# OneStep.net
KiCad netlist of a schematic drawn in Altium Designer
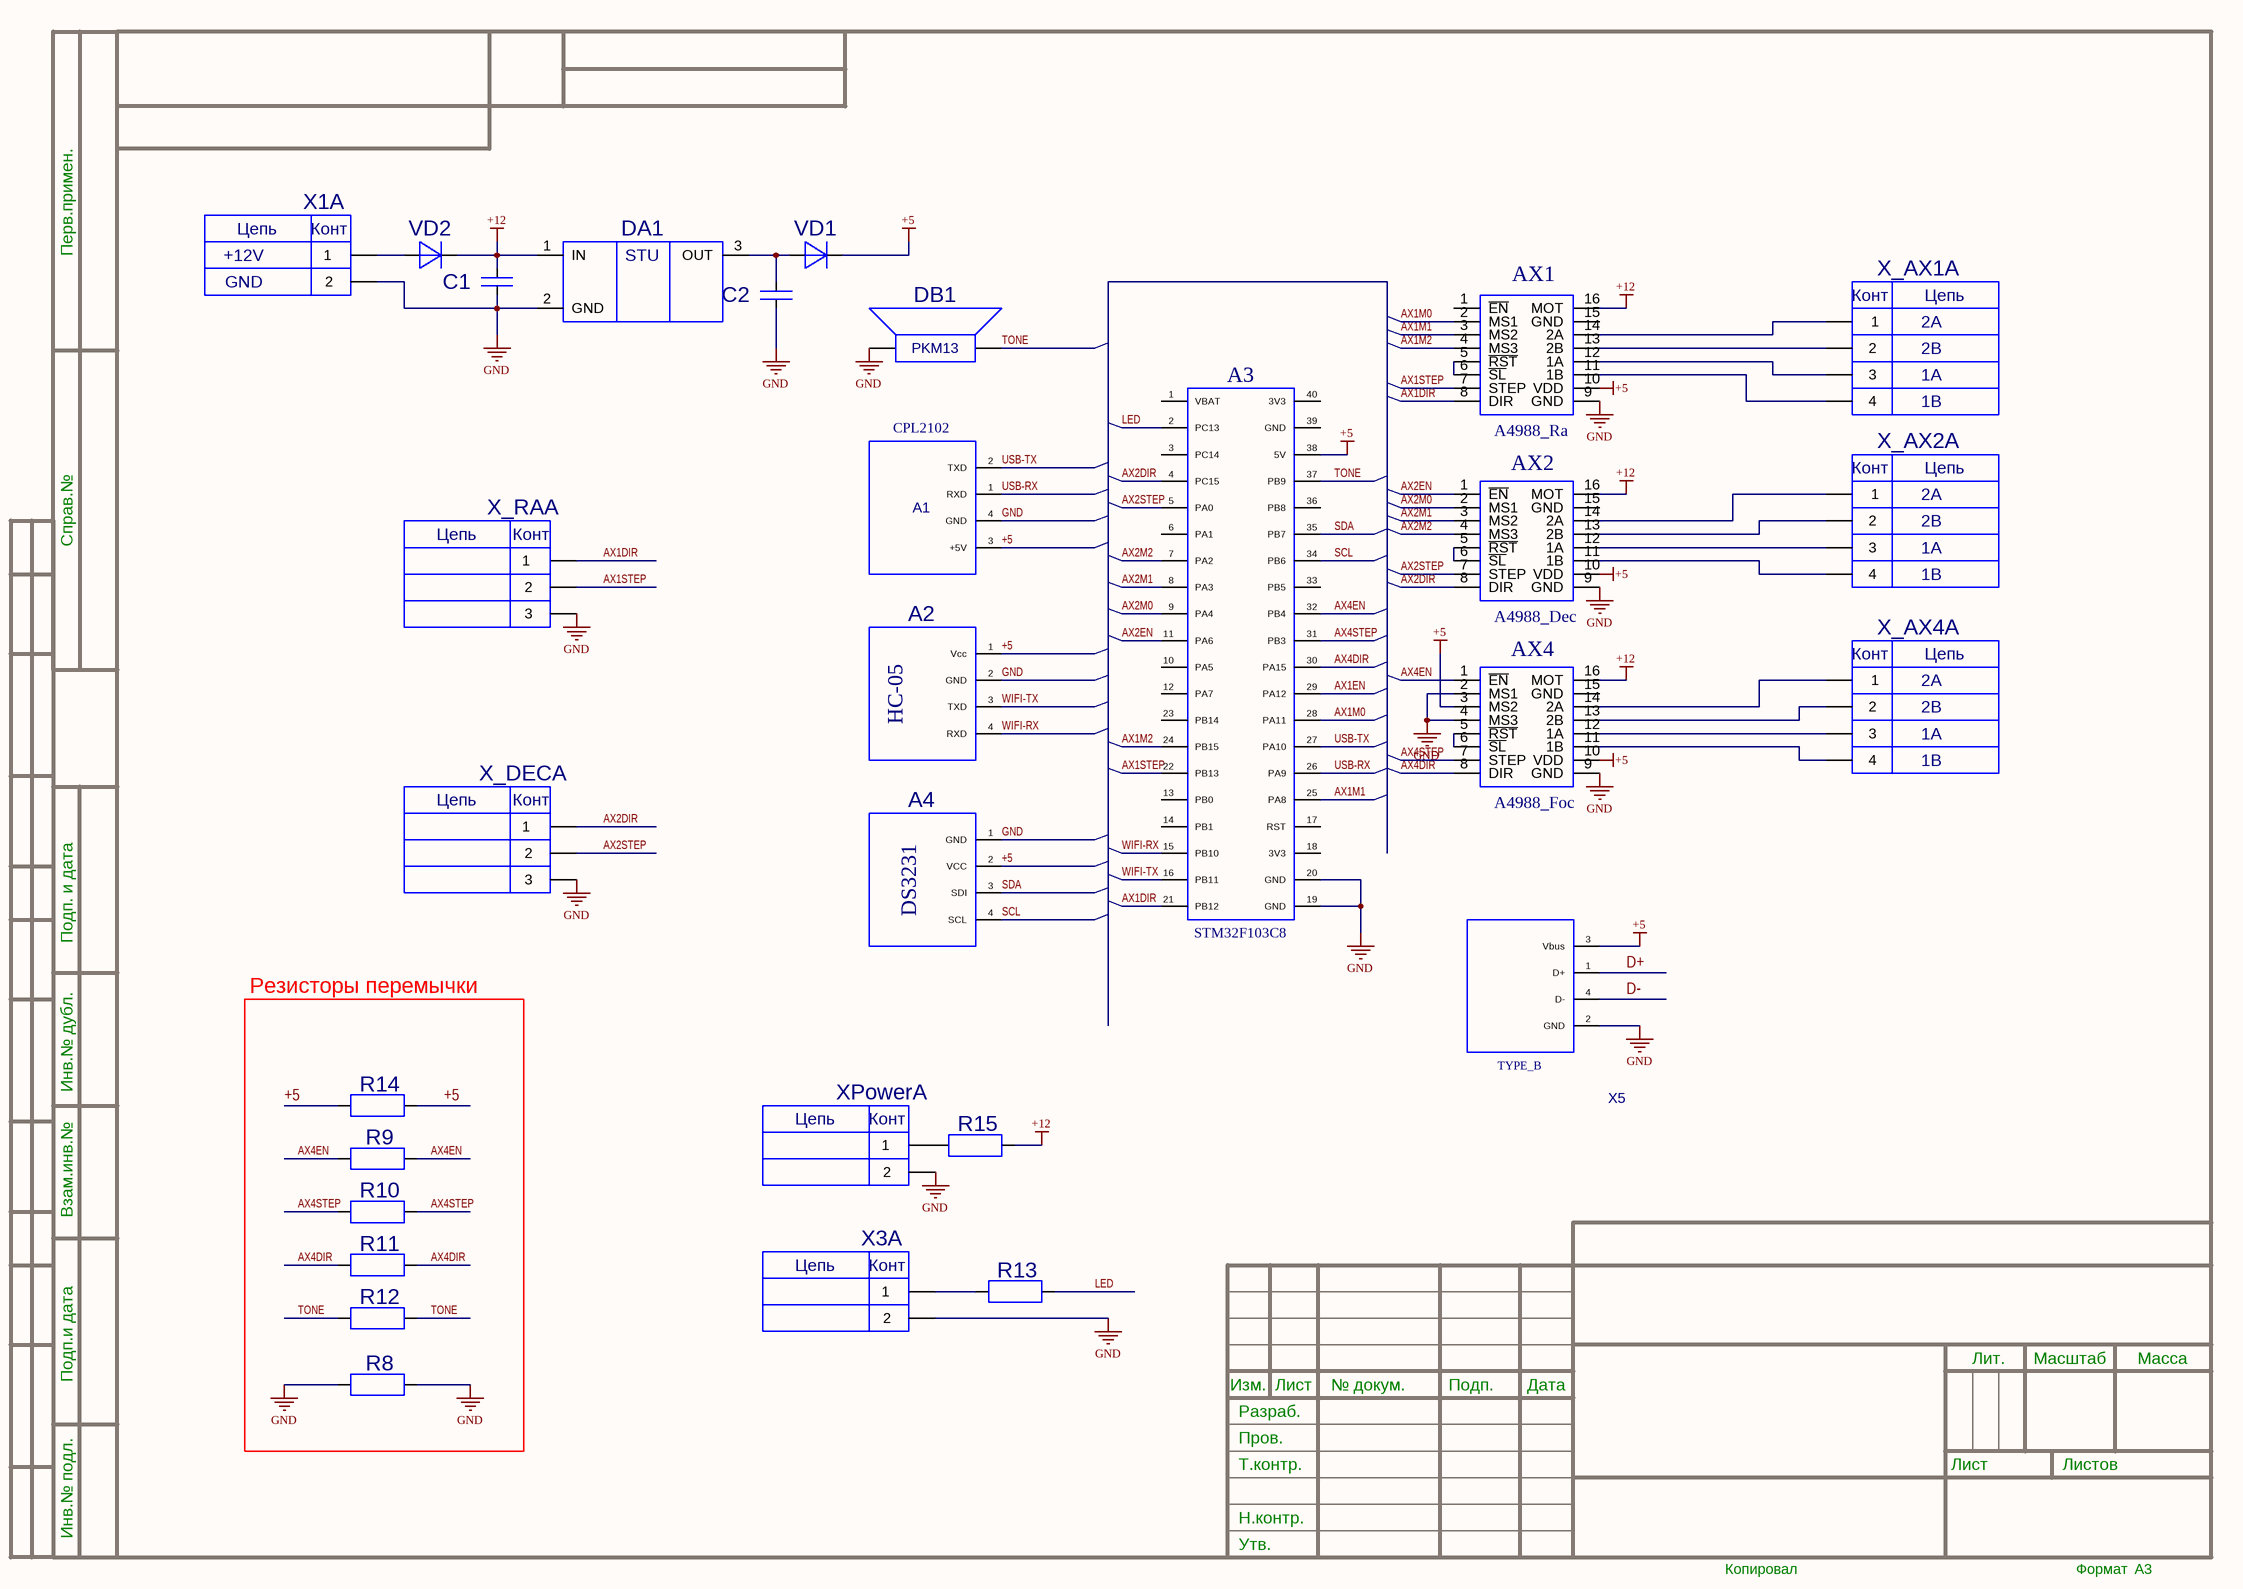
[diagram p0: OneStep.SchDoc]

(export (version "E")
  (design (tool "Eeschema 10.0.6"))
  (components
    (comp (ref "A1")
      (value "CPL2102")
      (footprint "CP2102")
      (fields
        (field (name "MANUFACTURER") "Texas Instruments")
        (field (name "COMPONENTLINK1URL") "c:\\Dataseets\\Микросхемы\\По фирмам\\Avago Technologies\\HCPL-4100.pdf")
      )
      (libsource (lib "nanoArduino") (part "CPL2102"))
    )
    (comp (ref "A2")
      (value "HC-05")
      (footprint "HC-05")
      (fields
        (field (name "MANUFACTURER") "Texas Instruments")
        (field (name "COMPONENTLINK1URL") "c:\\Dataseets\\Микросхемы\\По фирмам\\Avago Technologies\\HCPL-4100.pdf")
      )
      (libsource (lib "nanoArduino") (part "HC-05"))
    )
    (comp (ref "A3")
      (value "STM32F103C8")
      (footprint "STM32BLUE_PILL")
      (fields
        (field (name "MANUFACTURER") "NXP")
        (field (name "COMPONENTLINK1URL") "c:\\Dataseets\\Микросхемы\\По фирмам\\Avago Technologies\\HCPL-4100.pdf")
      )
      (libsource (lib "Horizont_11_12_2017") (part "STM32BLUE_PILL"))
    )
    (comp (ref "A4")
      (value "DS3231")
      (footprint "DS3231")
      (fields
        (field (name "MANUFACTURER") "Texas Instruments")
        (field (name "COMPONENTLINK1URL") "c:\\Dataseets\\Микросхемы\\По фирмам\\Avago Technologies\\HCPL-4100.pdf")
      )
      (libsource (lib "nanoArduino") (part "DS3231"))
    )
    (comp (ref "AX1")
      (value "A4988_Ra")
      (footprint "A4899")
      (description "STEP Motor Driver")
      (fields
        (field (name "PART NUMBER") "DRV8825")
        (field (name "HELPURL") "D:\\Local_view\\PDM\\Справочники\\Перечень ЭРИ\\Документация\\max1316-max1326.pdf")
      )
      (libsource (lib "nanoArduino") (part "DRV8825"))
    )
    (comp (ref "AX2")
      (value "A4988_Dec")
      (footprint "A4899")
      (description "STEP Motor Driver")
      (fields
        (field (name "PART NUMBER") "DRV8825")
        (field (name "HELPURL") "D:\\Local_view\\PDM\\Справочники\\Перечень ЭРИ\\Документация\\max1316-max1326.pdf")
      )
      (libsource (lib "nanoArduino") (part "DRV8825"))
    )
    (comp (ref "AX4")
      (value "A4988_Foc")
      (footprint "A4899")
      (description "STEP Motor Driver")
      (fields
        (field (name "PART NUMBER") "DRV8825")
        (field (name "HELPURL") "D:\\Local_view\\PDM\\Справочники\\Перечень ЭРИ\\Документация\\max1316-max1326.pdf")
      )
      (libsource (lib "nanoArduino") (part "DRV8825"))
    )
    (comp (ref "C1")
      (value "4,7мкФ")
      (footprint "C1206H19")
      (description "Керамический ЧИП конденсатор")
      (fields
        (field (name "PART NUMBER") "1206 X7R 50В 4,7мкФ")
        (field (name "TOLERANCE") "±10%")
        (field (name "HELPURL") "D:\\local_view\\PDM\\Справочники\\Перечень ЭРИ\\Документация\\Конденсаторы\\Керамические\\ЧИП\\0201-1812_TY.pdf")
      )
      (libsource (lib "Library") (part "C_nonpolar"))
    )
    (comp (ref "C2")
      (value "4,7мкФ")
      (footprint "C1206H19")
      (description "Керамический ЧИП конденсатор")
      (fields
        (field (name "PART NUMBER") "1206 X7R 50В 4,7мкФ")
        (field (name "TOLERANCE") "±10%")
        (field (name "HELPURL") "D:\\local_view\\PDM\\Справочники\\Перечень ЭРИ\\Документация\\Конденсаторы\\Керамические\\ЧИП\\0201-1812_TY.pdf")
      )
      (libsource (lib "Library") (part "C_nonpolar"))
    )
    (comp (ref "DA1")
      (value "L7805CD2T")
      (footprint "D2PAK")
      (description "Positive voltage regulator")
      (fields
        (field (name "MANUFACTURER") "ST Microelectronics")
        (field (name "HELPURL") "D:\\local_view\\PDM\\Справочники\\Перечень ЭРИ\\Документация\\Микросхемы\\Линейные стабилизаторы напряжения\\L7800_STMicroelectronics.pdf")
      )
      (libsource (lib "Library") (part "STU"))
    )
    (comp (ref "DB1")
      (value "PKM13")
      (footprint "PKM13")
      (description "=Description")
      (libsource (lib "nanoArduino") (part "PKM13"))
    )
    (comp (ref "R8")
      (value "0 Ом")
      (footprint "R1206H07")
      (description "Постоянный ЧИП резистор")
      (fields
        (field (name "PART NUMBER") "1206 0 Ом±5%")
        (field (name "POWER") "0.25W")
        (field (name "HELPURL") "D:\\Local_view\\PDM\\Справочники\\Перечень ЭРИ\\Документация\\Резисторы\\Постоянные\\ЧИП\\RC1206_yageo.pdf")
      )
      (libsource (lib "Library") (part "R"))
    )
    (comp (ref "R9")
      (value "0 Ом")
      (footprint "R1206H07")
      (description "Постоянный ЧИП резистор")
      (fields
        (field (name "PART NUMBER") "1206 0 Ом±5%")
        (field (name "POWER") "0.25W")
        (field (name "HELPURL") "D:\\Local_view\\PDM\\Справочники\\Перечень ЭРИ\\Документация\\Резисторы\\Постоянные\\ЧИП\\RC1206_yageo.pdf")
      )
      (libsource (lib "Library") (part "R"))
    )
    (comp (ref "R10")
      (value "0 Ом")
      (footprint "R1206H07")
      (description "Постоянный ЧИП резистор")
      (fields
        (field (name "PART NUMBER") "1206 0 Ом±5%")
        (field (name "POWER") "0.25W")
        (field (name "HELPURL") "D:\\Local_view\\PDM\\Справочники\\Перечень ЭРИ\\Документация\\Резисторы\\Постоянные\\ЧИП\\RC1206_yageo.pdf")
      )
      (libsource (lib "Library") (part "R"))
    )
    (comp (ref "R11")
      (value "0 Ом")
      (footprint "R1206H07")
      (description "Постоянный ЧИП резистор")
      (fields
        (field (name "PART NUMBER") "1206 0 Ом±5%")
        (field (name "POWER") "0.25W")
        (field (name "HELPURL") "D:\\Local_view\\PDM\\Справочники\\Перечень ЭРИ\\Документация\\Резисторы\\Постоянные\\ЧИП\\RC1206_yageo.pdf")
      )
      (libsource (lib "Library") (part "R"))
    )
    (comp (ref "R12")
      (value "0 Ом")
      (footprint "R1206H07")
      (description "Постоянный ЧИП резистор")
      (fields
        (field (name "PART NUMBER") "1206 0 Ом±5%")
        (field (name "POWER") "0.25W")
        (field (name "HELPURL") "D:\\Local_view\\PDM\\Справочники\\Перечень ЭРИ\\Документация\\Резисторы\\Постоянные\\ЧИП\\RC1206_yageo.pdf")
      )
      (libsource (lib "Library") (part "R"))
    )
    (comp (ref "R13")
      (value "0 Ом")
      (footprint "R1206H07")
      (description "Постоянный ЧИП резистор")
      (fields
        (field (name "PART NUMBER") "1206 0 Ом±5%")
        (field (name "POWER") "0.25W")
        (field (name "HELPURL") "D:\\Local_view\\PDM\\Справочники\\Перечень ЭРИ\\Документация\\Резисторы\\Постоянные\\ЧИП\\RC1206_yageo.pdf")
      )
      (libsource (lib "Library") (part "R"))
    )
    (comp (ref "R14")
      (value "0 Ом")
      (footprint "R1206H07")
      (description "Постоянный ЧИП резистор")
      (fields
        (field (name "PART NUMBER") "1206 0 Ом±5%")
        (field (name "POWER") "0.25W")
        (field (name "HELPURL") "D:\\Local_view\\PDM\\Справочники\\Перечень ЭРИ\\Документация\\Резисторы\\Постоянные\\ЧИП\\RC1206_yageo.pdf")
      )
      (libsource (lib "Library") (part "R"))
    )
    (comp (ref "R15")
      (value "24кОм")
      (footprint "R1206H07")
      (description "Постоянный ЧИП резистор")
      (fields
        (field (name "PART NUMBER") "1206 24кОм±5%")
        (field (name "POWER") "0.25W")
        (field (name "HELPURL") "D:\\Local_view\\PDM\\Справочники\\Перечень ЭРИ\\Документация\\Резисторы\\Постоянные\\ЧИП\\RC1206_yageo.pdf")
      )
      (libsource (lib "Library") (part "R"))
    )
    (comp (ref "VD1")
      (value "US1J")
      (footprint "SMA")
      (description "Surface Mount Ultra Fast Rectifier")
      (fields
        (field (name "MANUFACTURER") "Vishay")
        (field (name "HELPURL") "D:\\local_view\\PDM\\Справочники\\Перечень ЭРИ\\Документация\\Диоды\\Выпрямительные и импульсные диоды\\US1A-US1M_Vishay.pdf")
      )
      (libsource (lib "Library") (part "VD"))
    )
    (comp (ref "VD2")
      (value "US1J")
      (footprint "SMA")
      (description "Surface Mount Ultra Fast Rectifier")
      (fields
        (field (name "MANUFACTURER") "Vishay")
        (field (name "HELPURL") "D:\\local_view\\PDM\\Справочники\\Перечень ЭРИ\\Документация\\Диоды\\Выпрямительные и импульсные диоды\\US1A-US1M_Vishay.pdf")
      )
      (libsource (lib "Library") (part "VD"))
    )
    (comp (ref "X1")
      (value "PLS-02")
      (footprint "PLS-02")
      (description "Вилка на плату прямая шаг 2,54 мм 1 ряд")
      (fields
        (field (name "HELPURL") "D:\\Local_view\\PDM\\Справочники\\Перечень ЭРИ\\Документация\\Соединители\\Прямоугольные\\pld_pls.pdf")
      )
      (libsource (lib "Library") (part "CONT2"))
    )
    (comp (ref "X3")
      (value "PLS-02")
      (footprint "PLS-02")
      (description "Вилка на плату прямая шаг 2,54 мм 1 ряд")
      (fields
        (field (name "HELPURL") "D:\\Local_view\\PDM\\Справочники\\Перечень ЭРИ\\Документация\\Соединители\\Прямоугольные\\pld_pls.pdf")
      )
      (libsource (lib "Library") (part "CONT2"))
    )
    (comp (ref "X5")
      (value "TYPE_B")
      (footprint "Type_B")
      (description "USB_type_B")
      (fields
        (field (name "MANUFACTURER") "Texas Instruments")
        (field (name "VALUESCH") "TYPE_B")
        (field (name "COMPONENTLINK1URL") "c:\\Dataseets\\Микросхемы\\По фирмам\\Avago Technologies\\HCPL-4100.pdf")
      )
      (libsource (lib "nanoArduino") (part "USB_type_B"))
    )
    (comp (ref "XPower")
      (value "PLS-02")
      (footprint "PLS-02")
      (description "Вилка на плату прямая шаг 2,54 мм 1 ряд")
      (fields
        (field (name "HELPURL") "D:\\Local_view\\PDM\\Справочники\\Перечень ЭРИ\\Документация\\Соединители\\Прямоугольные\\pld_pls.pdf")
      )
      (libsource (lib "Library") (part "CONT2"))
    )
    (comp (ref "X_AX1")
      (value "PLS-04")
      (footprint "PLS-04")
      (description "Вилка на плату прямая шаг 2,54 мм 1 ряд")
      (fields
        (field (name "HELPURL") "D:\\Local_view\\PDM\\Справочники\\Перечень ЭРИ\\Документация\\Соединители\\Прямоугольные\\pld_pls.pdf")
      )
      (libsource (lib "Library") (part "CONT4"))
    )
    (comp (ref "X_AX2")
      (value "PLS-04")
      (footprint "PLS-04")
      (description "Вилка на плату прямая шаг 2,54 мм 1 ряд")
      (fields
        (field (name "HELPURL") "D:\\Local_view\\PDM\\Справочники\\Перечень ЭРИ\\Документация\\Соединители\\Прямоугольные\\pld_pls.pdf")
      )
      (libsource (lib "Library") (part "CONT4"))
    )
    (comp (ref "X_AX4")
      (value "PLS-04")
      (footprint "PLS-04")
      (description "Вилка на плату прямая шаг 2,54 мм 1 ряд")
      (fields
        (field (name "HELPURL") "D:\\Local_view\\PDM\\Справочники\\Перечень ЭРИ\\Документация\\Соединители\\Прямоугольные\\pld_pls.pdf")
      )
      (libsource (lib "Library") (part "CONT4"))
    )
    (comp (ref "X_DEC")
      (value "DG128-5.0-03P")
      (footprint "DG128-5.0-03")
      (description "Винтовой клеммник, \r\n3 контакта")
      (fields
        (field (name "PART NUMBER") "DG128-5.0-03P-14")
        (field (name "MANUFACTURER") "DEGSON")
        (field (name "HELPURL") "D:\\Local_view\\PDM\\Справочники\\Перечень ЭРИ\\Документация\\Соединители\\Клеммники\\DG128-5.0.pdf")
      )
      (libsource (lib "Library") (part "CONT3"))
    )
    (comp (ref "X_RA")
      (value "DG128-5.0-03P")
      (footprint "DG128-5.0-03")
      (description "Винтовой клеммник, \r\n3 контакта")
      (fields
        (field (name "PART NUMBER") "DG128-5.0-03P-14")
        (field (name "MANUFACTURER") "DEGSON")
        (field (name "HELPURL") "D:\\Local_view\\PDM\\Справочники\\Перечень ЭРИ\\Документация\\Соединители\\Клеммники\\DG128-5.0.pdf")
      )
      (libsource (lib "Library") (part "CONT3"))
    )
  )
  (nets
    (net (code "1") (name "+5") (class "Default")
      (node (ref "A1") (pin "3") (pinfunction "+5V_3") (pintype "passive"))
      (node (ref "A2") (pin "1") (pinfunction "Vcc_1") (pintype "passive"))
      (node (ref "A3") (pin "38") (pinfunction "5V_38") (pintype "passive"))
      (node (ref "A4") (pin "2") (pinfunction "VCC_2") (pintype "passive"))
      (node (ref "AX1") (pin "10") (pinfunction "VDD_10") (pintype "passive"))
      (node (ref "AX2") (pin "10") (pinfunction "VDD_10") (pintype "passive"))
      (node (ref "AX4") (pin "10") (pinfunction "VDD_10") (pintype "passive"))
      (node (ref "AX4") (pin "3") (pinfunction "MS2_3") (pintype "passive"))
      (node (ref "R14") (pin "1") (pinfunction "1_1") (pintype "passive"))
      (node (ref "R14") (pin "2") (pinfunction "2_2") (pintype "passive"))
      (node (ref "VD1") (pin "2") (pinfunction "-_2") (pintype "passive"))
      (node (ref "X5") (pin "3") (pinfunction "Vbus_3") (pintype "passive"))
    )
    (net (code "2") (name "+12") (class "Default")
      (node (ref "AX1") (pin "16") (pinfunction "MOT_16") (pintype "passive"))
      (node (ref "AX2") (pin "16") (pinfunction "MOT_16") (pintype "passive"))
      (node (ref "AX4") (pin "16") (pinfunction "MOT_16") (pintype "passive"))
      (node (ref "C1") (pin "2") (pinfunction "2_2") (pintype "passive"))
      (node (ref "DA1") (pin "1") (pinfunction "IN_1") (pintype "passive"))
      (node (ref "R15") (pin "2") (pinfunction "2_2") (pintype "passive"))
      (node (ref "VD2") (pin "2") (pinfunction "-_2") (pintype "passive"))
    )
    (net (code "3") (name "/AX1DIR") (class "Default")
      (node (ref "A3") (pin "21") (pinfunction "PB12_21") (pintype "passive"))
      (node (ref "AX1") (pin "8") (pinfunction "DIR_8") (pintype "passive"))
      (node (ref "X_RA") (pin "1") (pinfunction "1_1") (pintype "passive"))
    )
    (net (code "4") (name "/AX1EN") (class "Default")
      (node (ref "A3") (pin "29") (pinfunction "PA12_29") (pintype "passive"))
    )
    (net (code "5") (name "/AX1M0") (class "Default")
      (node (ref "A3") (pin "28") (pinfunction "PA11_28") (pintype "passive"))
      (node (ref "AX1") (pin "2") (pinfunction "MS1_2") (pintype "passive"))
    )
    (net (code "6") (name "/AX1M1") (class "Default")
      (node (ref "A3") (pin "25") (pinfunction "PA8_25") (pintype "passive"))
      (node (ref "AX1") (pin "3") (pinfunction "MS2_3") (pintype "passive"))
    )
    (net (code "7") (name "/AX1M2") (class "Default")
      (node (ref "A3") (pin "24") (pinfunction "PB15_24") (pintype "passive"))
      (node (ref "AX1") (pin "4") (pinfunction "MS3_4") (pintype "passive"))
    )
    (net (code "8") (name "/AX1STEP") (class "Default")
      (node (ref "A3") (pin "22") (pinfunction "PB13_22") (pintype "passive"))
      (node (ref "AX1") (pin "7") (pinfunction "STEP_7") (pintype "passive"))
      (node (ref "X_RA") (pin "2") (pinfunction "2_2") (pintype "passive"))
    )
    (net (code "9") (name "/AX2DIR") (class "Default")
      (node (ref "A3") (pin "4") (pinfunction "PC15_4") (pintype "passive"))
      (node (ref "AX2") (pin "8") (pinfunction "DIR_8") (pintype "passive"))
      (node (ref "X_DEC") (pin "1") (pinfunction "1_1") (pintype "passive"))
    )
    (net (code "10") (name "/AX2EN") (class "Default")
      (node (ref "A3") (pin "11") (pinfunction "PA6_11") (pintype "passive"))
      (node (ref "AX2") (pin "1") (pinfunction "EN_1") (pintype "passive"))
    )
    (net (code "11") (name "/AX2M0") (class "Default")
      (node (ref "A3") (pin "9") (pinfunction "PA4_9") (pintype "passive"))
      (node (ref "AX2") (pin "2") (pinfunction "MS1_2") (pintype "passive"))
    )
    (net (code "12") (name "/AX2M1") (class "Default")
      (node (ref "A3") (pin "8") (pinfunction "PA3_8") (pintype "passive"))
      (node (ref "AX2") (pin "3") (pinfunction "MS2_3") (pintype "passive"))
    )
    (net (code "13") (name "/AX2M2") (class "Default")
      (node (ref "A3") (pin "7") (pinfunction "PA2_7") (pintype "passive"))
      (node (ref "AX2") (pin "4") (pinfunction "MS3_4") (pintype "passive"))
    )
    (net (code "14") (name "/AX2STEP") (class "Default")
      (node (ref "A3") (pin "5") (pinfunction "PA0_5") (pintype "passive"))
      (node (ref "AX2") (pin "7") (pinfunction "STEP_7") (pintype "passive"))
      (node (ref "X_DEC") (pin "2") (pinfunction "2_2") (pintype "passive"))
    )
    (net (code "15") (name "/AX4DIR") (class "Default")
      (node (ref "A3") (pin "30") (pinfunction "PA15_30") (pintype "passive"))
      (node (ref "AX4") (pin "8") (pinfunction "DIR_8") (pintype "passive"))
      (node (ref "R11") (pin "1") (pinfunction "1_1") (pintype "passive"))
      (node (ref "R11") (pin "2") (pinfunction "2_2") (pintype "passive"))
    )
    (net (code "16") (name "/AX4EN") (class "Default")
      (node (ref "A3") (pin "32") (pinfunction "PB4_32") (pintype "passive"))
      (node (ref "AX4") (pin "1") (pinfunction "EN_1") (pintype "passive"))
      (node (ref "R9") (pin "1") (pinfunction "1_1") (pintype "passive"))
      (node (ref "R9") (pin "2") (pinfunction "2_2") (pintype "passive"))
    )
    (net (code "17") (name "/AX4STEP") (class "Default")
      (node (ref "A3") (pin "31") (pinfunction "PB3_31") (pintype "passive"))
      (node (ref "AX4") (pin "7") (pinfunction "STEP_7") (pintype "passive"))
      (node (ref "R10") (pin "1") (pinfunction "1_1") (pintype "passive"))
      (node (ref "R10") (pin "2") (pinfunction "2_2") (pintype "passive"))
    )
    (net (code "18") (name "/D+") (class "Default")
      (node (ref "X5") (pin "1") (pinfunction "D+_1") (pintype "passive"))
    )
    (net (code "19") (name "/D-") (class "Default")
      (node (ref "X5") (pin "4") (pinfunction "D-_4") (pintype "passive"))
    )
    (net (code "20") (name "/LED") (class "Default")
      (node (ref "A3") (pin "2") (pinfunction "PC13_2") (pintype "passive"))
      (node (ref "R13") (pin "2") (pinfunction "2_2") (pintype "passive"))
    )
    (net (code "21") (name "/SCL") (class "Default")
      (node (ref "A3") (pin "34") (pinfunction "PB6_34") (pintype "passive"))
      (node (ref "A4") (pin "4") (pinfunction "SCL_4") (pintype "passive"))
    )
    (net (code "22") (name "/SDA") (class "Default")
      (node (ref "A3") (pin "35") (pinfunction "PB7_35") (pintype "passive"))
      (node (ref "A4") (pin "3") (pinfunction "SDI_3") (pintype "passive"))
    )
    (net (code "23") (name "/TONE") (class "Default")
      (node (ref "A3") (pin "37") (pinfunction "PB9_37") (pintype "passive"))
      (node (ref "DB1") (pin "2") (pinfunction "2_2") (pintype "passive"))
      (node (ref "R12") (pin "1") (pinfunction "1_1") (pintype "passive"))
      (node (ref "R12") (pin "2") (pinfunction "2_2") (pintype "passive"))
    )
    (net (code "24") (name "/USB-RX") (class "Default")
      (node (ref "A1") (pin "1") (pinfunction "RXD_1") (pintype "passive"))
      (node (ref "A3") (pin "26") (pinfunction "PA9_26") (pintype "passive"))
    )
    (net (code "25") (name "/USB-TX") (class "Default")
      (node (ref "A1") (pin "2") (pinfunction "TXD_2") (pintype "passive"))
      (node (ref "A3") (pin "27") (pinfunction "PA10_27") (pintype "passive"))
    )
    (net (code "26") (name "/WIFI-RX") (class "Default")
      (node (ref "A2") (pin "4") (pinfunction "RXD_4") (pintype "passive"))
      (node (ref "A3") (pin "15") (pinfunction "PB10_15") (pintype "passive"))
    )
    (net (code "27") (name "/WIFI-TX") (class "Default")
      (node (ref "A2") (pin "3") (pinfunction "TXD_3") (pintype "passive"))
      (node (ref "A3") (pin "16") (pinfunction "PB11_16") (pintype "passive"))
    )
    (net (code "28") (name "GND") (class "Default")
      (node (ref "A1") (pin "4") (pinfunction "GND_4") (pintype "passive"))
      (node (ref "A2") (pin "2") (pinfunction "GND_2") (pintype "passive"))
      (node (ref "A3") (pin "19") (pinfunction "GND_19") (pintype "passive"))
      (node (ref "A3") (pin "20") (pinfunction "GND_20") (pintype "passive"))
      (node (ref "A4") (pin "1") (pinfunction "GND_1") (pintype "passive"))
      (node (ref "AX1") (pin "9") (pinfunction "GND_9") (pintype "passive"))
      (node (ref "AX2") (pin "9") (pinfunction "GND_9") (pintype "passive"))
      (node (ref "AX4") (pin "2") (pinfunction "MS1_2") (pintype "passive"))
      (node (ref "AX4") (pin "4") (pinfunction "MS3_4") (pintype "passive"))
      (node (ref "AX4") (pin "9") (pinfunction "GND_9") (pintype "passive"))
      (node (ref "C1") (pin "1") (pinfunction "1_1") (pintype "passive"))
      (node (ref "C2") (pin "1") (pinfunction "1_1") (pintype "passive"))
      (node (ref "DA1") (pin "2") (pinfunction "GND_2") (pintype "passive"))
      (node (ref "DB1") (pin "1") (pinfunction "1_1") (pintype "passive"))
      (node (ref "R8") (pin "1") (pinfunction "1_1") (pintype "passive"))
      (node (ref "R8") (pin "2") (pinfunction "2_2") (pintype "passive"))
      (node (ref "X1") (pin "2") (pinfunction "2_2") (pintype "passive"))
      (node (ref "X3") (pin "2") (pinfunction "2_2") (pintype "passive"))
      (node (ref "X5") (pin "2") (pinfunction "GND_2") (pintype "passive"))
      (node (ref "XPower") (pin "2") (pinfunction "2_2") (pintype "passive"))
      (node (ref "X_DEC") (pin "3") (pinfunction "3_3") (pintype "passive"))
      (node (ref "X_RA") (pin "3") (pinfunction "3_3") (pintype "passive"))
    )
    (net (code "29") (name "Net-(AX1-1A)") (class "Default")
      (node (ref "AX1") (pin "12") (pinfunction "1A_12") (pintype "passive"))
      (node (ref "X_AX1") (pin "3") (pinfunction "3_3") (pintype "passive"))
    )
    (net (code "30") (name "Net-(AX1-1B)") (class "Default")
      (node (ref "AX1") (pin "11") (pinfunction "1B_11") (pintype "passive"))
      (node (ref "X_AX1") (pin "4") (pinfunction "4_4") (pintype "passive"))
    )
    (net (code "31") (name "Net-(AX1-2A)") (class "Default")
      (node (ref "AX1") (pin "14") (pinfunction "2A_14") (pintype "passive"))
      (node (ref "X_AX1") (pin "1") (pinfunction "1_1") (pintype "passive"))
    )
    (net (code "32") (name "Net-(AX1-2B)") (class "Default")
      (node (ref "AX1") (pin "13") (pinfunction "2B_13") (pintype "passive"))
      (node (ref "X_AX1") (pin "2") (pinfunction "2_2") (pintype "passive"))
    )
    (net (code "33") (name "Net-(AX1-RST)") (class "Default")
      (node (ref "AX1") (pin "5") (pinfunction "RST_5") (pintype "passive"))
      (node (ref "AX1") (pin "6") (pinfunction "SL_6") (pintype "passive"))
    )
    (net (code "34") (name "Net-(AX2-1A)") (class "Default")
      (node (ref "AX2") (pin "12") (pinfunction "1A_12") (pintype "passive"))
      (node (ref "X_AX2") (pin "3") (pinfunction "3_3") (pintype "passive"))
    )
    (net (code "35") (name "Net-(AX2-1B)") (class "Default")
      (node (ref "AX2") (pin "11") (pinfunction "1B_11") (pintype "passive"))
      (node (ref "X_AX2") (pin "4") (pinfunction "4_4") (pintype "passive"))
    )
    (net (code "36") (name "Net-(AX2-2A)") (class "Default")
      (node (ref "AX2") (pin "14") (pinfunction "2A_14") (pintype "passive"))
      (node (ref "X_AX2") (pin "1") (pinfunction "1_1") (pintype "passive"))
    )
    (net (code "37") (name "Net-(AX2-2B)") (class "Default")
      (node (ref "AX2") (pin "13") (pinfunction "2B_13") (pintype "passive"))
      (node (ref "X_AX2") (pin "2") (pinfunction "2_2") (pintype "passive"))
    )
    (net (code "38") (name "Net-(AX2-RST)") (class "Default")
      (node (ref "AX2") (pin "5") (pinfunction "RST_5") (pintype "passive"))
      (node (ref "AX2") (pin "6") (pinfunction "SL_6") (pintype "passive"))
    )
    (net (code "39") (name "Net-(AX4-1A)") (class "Default")
      (node (ref "AX4") (pin "12") (pinfunction "1A_12") (pintype "passive"))
      (node (ref "X_AX4") (pin "3") (pinfunction "3_3") (pintype "passive"))
    )
    (net (code "40") (name "Net-(AX4-1B)") (class "Default")
      (node (ref "AX4") (pin "11") (pinfunction "1B_11") (pintype "passive"))
      (node (ref "X_AX4") (pin "4") (pinfunction "4_4") (pintype "passive"))
    )
    (net (code "41") (name "Net-(AX4-2A)") (class "Default")
      (node (ref "AX4") (pin "14") (pinfunction "2A_14") (pintype "passive"))
      (node (ref "X_AX4") (pin "1") (pinfunction "1_1") (pintype "passive"))
    )
    (net (code "42") (name "Net-(AX4-2B)") (class "Default")
      (node (ref "AX4") (pin "13") (pinfunction "2B_13") (pintype "passive"))
      (node (ref "X_AX4") (pin "2") (pinfunction "2_2") (pintype "passive"))
    )
    (net (code "43") (name "Net-(AX4-RST)") (class "Default")
      (node (ref "AX4") (pin "5") (pinfunction "RST_5") (pintype "passive"))
      (node (ref "AX4") (pin "6") (pinfunction "SL_6") (pintype "passive"))
    )
    (net (code "44") (name "Net-(DA1-OUT)") (class "Default")
      (node (ref "C2") (pin "2") (pinfunction "2_2") (pintype "passive"))
      (node (ref "DA1") (pin "3") (pinfunction "OUT_3") (pintype "passive"))
      (node (ref "VD1") (pin "1") (pinfunction "+_1") (pintype "passive"))
    )
    (net (code "45") (name "Net-(R13-Pad1)") (class "Default")
      (node (ref "R13") (pin "1") (pinfunction "1_1") (pintype "passive"))
      (node (ref "X3") (pin "1") (pinfunction "1_1") (pintype "passive"))
    )
    (net (code "46") (name "Net-(R15-Pad1)") (class "Default")
      (node (ref "R15") (pin "1") (pinfunction "1_1") (pintype "passive"))
      (node (ref "XPower") (pin "1") (pinfunction "1_1") (pintype "passive"))
    )
    (net (code "47") (name "Net-(VD2-+)") (class "Default")
      (node (ref "VD2") (pin "1") (pinfunction "+_1") (pintype "passive"))
      (node (ref "X1") (pin "1") (pinfunction "1_1") (pintype "passive"))
    )
    (net (code "48") (name "unconnected-(A3-3V3-Pad18)") (class "Default")
      (node (ref "A3") (pin "18") (pinfunction "3V3_18") (pintype "passive"))
    )
    (net (code "49") (name "unconnected-(A3-3V3-Pad40)") (class "Default")
      (node (ref "A3") (pin "40") (pinfunction "3V3_40") (pintype "passive"))
    )
    (net (code "50") (name "unconnected-(A3-GND-Pad39)") (class "Default")
      (node (ref "A3") (pin "39") (pinfunction "GND_39") (pintype "passive"))
    )
    (net (code "51") (name "unconnected-(A3-PA1-Pad6)") (class "Default")
      (node (ref "A3") (pin "6") (pinfunction "PA1_6") (pintype "passive"))
    )
    (net (code "52") (name "unconnected-(A3-PA5-Pad10)") (class "Default")
      (node (ref "A3") (pin "10") (pinfunction "PA5_10") (pintype "passive"))
    )
    (net (code "53") (name "unconnected-(A3-PA7-Pad12)") (class "Default")
      (node (ref "A3") (pin "12") (pinfunction "PA7_12") (pintype "passive"))
    )
    (net (code "54") (name "unconnected-(A3-PB0-Pad13)") (class "Default")
      (node (ref "A3") (pin "13") (pinfunction "PB0_13") (pintype "passive"))
    )
    (net (code "55") (name "unconnected-(A3-PB1-Pad14)") (class "Default")
      (node (ref "A3") (pin "14") (pinfunction "PB1_14") (pintype "passive"))
    )
    (net (code "56") (name "unconnected-(A3-PB5-Pad33)") (class "Default")
      (node (ref "A3") (pin "33") (pinfunction "PB5_33") (pintype "passive"))
    )
    (net (code "57") (name "unconnected-(A3-PB8-Pad36)") (class "Default")
      (node (ref "A3") (pin "36") (pinfunction "PB8_36") (pintype "passive"))
    )
    (net (code "58") (name "unconnected-(A3-PB14-Pad23)") (class "Default")
      (node (ref "A3") (pin "23") (pinfunction "PB14_23") (pintype "passive"))
    )
    (net (code "59") (name "unconnected-(A3-PC14-Pad3)") (class "Default")
      (node (ref "A3") (pin "3") (pinfunction "PC14_3") (pintype "passive"))
    )
    (net (code "60") (name "unconnected-(A3-RST-Pad17)") (class "Default")
      (node (ref "A3") (pin "17") (pinfunction "RST_17") (pintype "passive"))
    )
    (net (code "61") (name "unconnected-(A3-VBAT-Pad1)") (class "Default")
      (node (ref "A3") (pin "1") (pinfunction "VBAT_1") (pintype "passive"))
    )
    (net (code "62") (name "unconnected-(AX1-EN-Pad1)") (class "Default")
      (node (ref "AX1") (pin "1") (pinfunction "EN_1") (pintype "passive"))
    )
    (net (code "63") (name "unconnected-(AX1-GND-Pad15)") (class "Default")
      (node (ref "AX1") (pin "15") (pinfunction "GND_15") (pintype "passive"))
    )
    (net (code "64") (name "unconnected-(AX2-GND-Pad15)") (class "Default")
      (node (ref "AX2") (pin "15") (pinfunction "GND_15") (pintype "passive"))
    )
    (net (code "65") (name "unconnected-(AX4-GND-Pad15)") (class "Default")
      (node (ref "AX4") (pin "15") (pinfunction "GND_15") (pintype "passive"))
    )
  )
)
